# HRT.net
KiCad netlist of a schematic drawn in Altium Designer
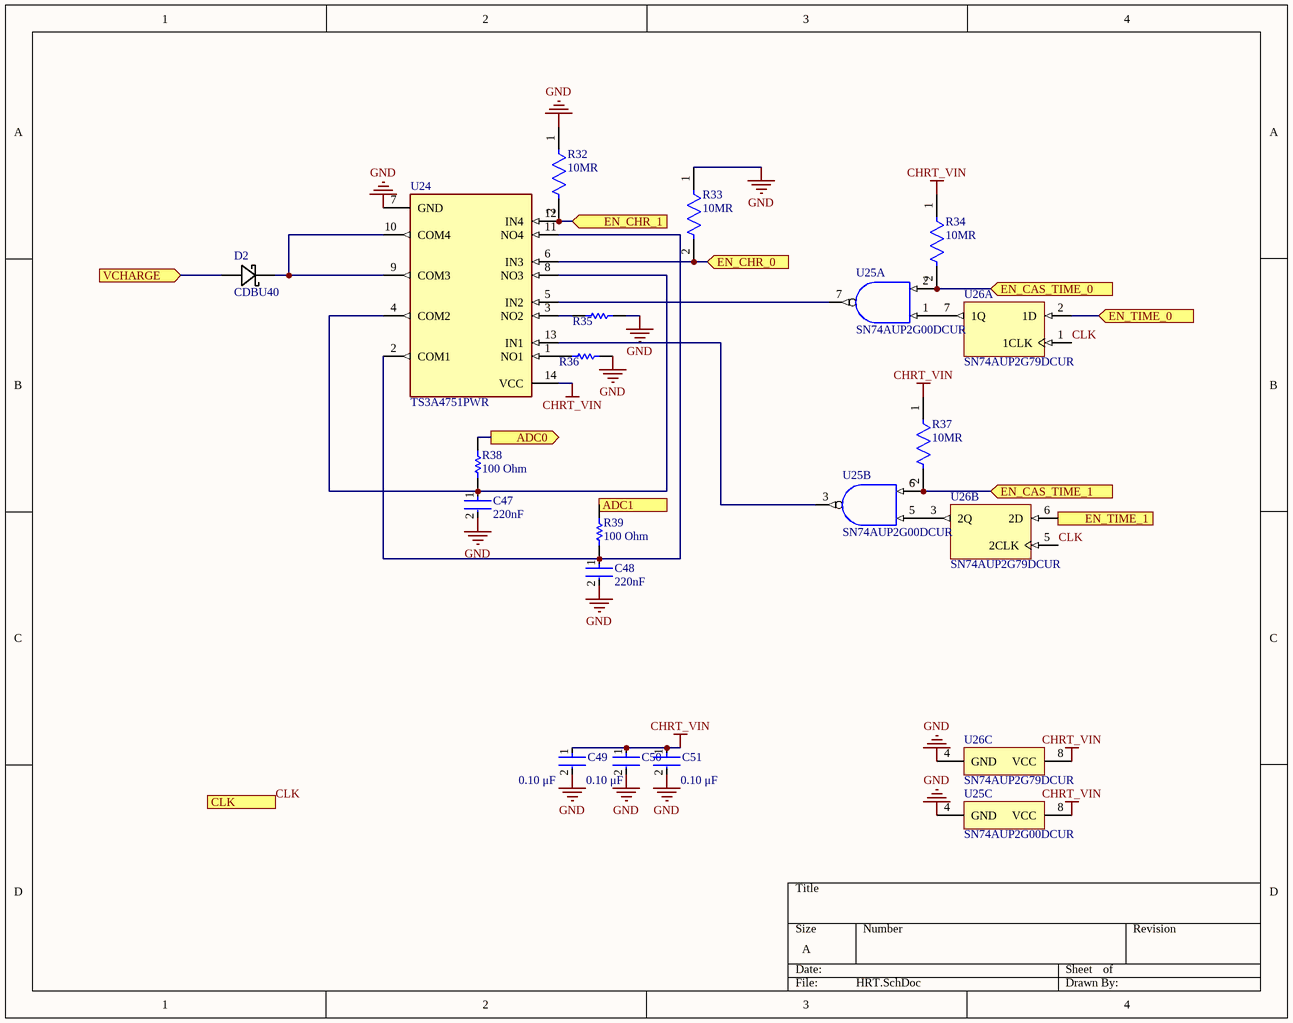
[diagram p0: HRT.SchDoc]

(export (version "E")
  (design (tool "Eeschema 10.0.6"))
  (components
    (comp (ref "C47")
      (value "GRM155R71C224KA12D")
      (footprint "FP-GRM155-0_05-IPC_C")
      (description "Chip Multilayer Ceramic Capacitors for General Purpose, 0402, 0.22uF, X7R, 15%, 10%, 16V")
      (fields
        (field (name "CAPACITANCE") "220nF")
        (field (name "VOLTAGE") "16V")
        (field (name "TOLERANCE") "10%")
      )
      (libsource (lib "Altium Content Vault") (part "02cd4be3c70576c341d710602a673aa"))
    )
    (comp (ref "C48")
      (value "GRM155R71C224KA12D")
      (footprint "FP-GRM155-0_05-IPC_C")
      (description "Chip Multilayer Ceramic Capacitors for General Purpose, 0402, 0.22uF, X7R, 15%, 10%, 16V")
      (fields
        (field (name "CAPACITANCE") "220nF")
        (field (name "VOLTAGE") "16V")
        (field (name "TOLERANCE") "10%")
      )
      (libsource (lib "Altium Content Vault") (part "02cd4be3c70576c341d710602a673aa"))
    )
    (comp (ref "C49")
      (value "C0402C104K8PACTU")
      (footprint "FP-C0402-BB-MFG")
      (description "CAP CER 0.1UF 10V X5R 0402")
      (fields
        (field (name "CAPACITANCE") "0.10 μF")
        (field (name "MANUFACTURER") "Kemet")
        (field (name "TOLERANCE") "0.1")
      )
      (libsource (lib "Altium Content Vault") (part "b4654b650e69147ec39a6b967a45e02"))
    )
    (comp (ref "C50")
      (value "C0402C104K8PACTU")
      (footprint "FP-C0402-BB-MFG")
      (description "CAP CER 0.1UF 10V X5R 0402")
      (fields
        (field (name "CAPACITANCE") "0.10 μF")
        (field (name "MANUFACTURER") "Kemet")
        (field (name "TOLERANCE") "0.1")
      )
      (libsource (lib "Altium Content Vault") (part "b4654b650e69147ec39a6b967a45e02"))
    )
    (comp (ref "C51")
      (value "C0402C104K8PACTU")
      (footprint "FP-C0402-BB-MFG")
      (description "CAP CER 0.1UF 10V X5R 0402")
      (fields
        (field (name "CAPACITANCE") "0.10 μF")
        (field (name "MANUFACTURER") "Kemet")
        (field (name "TOLERANCE") "0.1")
      )
      (libsource (lib "Altium Content Vault") (part "b4654b650e69147ec39a6b967a45e02"))
    )
    (comp (ref "D2")
      (value "CDBU40")
      (footprint "CDBU")
      (description "No Description Available")
      (fields (field (name "COPYRIGHT") "Copyright (C) 2022 Ultra Librarian. All rights reserved."))
      (libsource (lib "CDBU40") (part "CDBU40"))
    )
    (comp (ref "R32")
      (value "CRCW040210M0JNED")
      (footprint "FP-CRCW0402-e3-IPC_C")
      (description "RES Thick Film, 10MΩ, 5%, 0.063W, 200ppm/°C, 0402")
      (fields (field (name "TOLERANCE") "5%") (field (name "RESISTANCE") "10MR"))
      (libsource (lib "Altium Content Vault") (part "1029c3af85768c4190bb7ad29bc67b5"))
    )
    (comp (ref "R33")
      (value "CRCW040210M0JNED")
      (footprint "FP-CRCW0402-e3-IPC_C")
      (description "RES Thick Film, 10MΩ, 5%, 0.063W, 200ppm/°C, 0402")
      (fields (field (name "TOLERANCE") "5%") (field (name "RESISTANCE") "10MR"))
      (libsource (lib "Altium Content Vault") (part "1029c3af85768c4190bb7ad29bc67b5"))
    )
    (comp (ref "R34")
      (value "CRCW040210M0JNED")
      (footprint "FP-CRCW0402-e3-IPC_C")
      (description "RES Thick Film, 10MΩ, 5%, 0.063W, 200ppm/°C, 0402")
      (fields (field (name "TOLERANCE") "5%") (field (name "RESISTANCE") "10MR"))
      (libsource (lib "Altium Content Vault") (part "1029c3af85768c4190bb7ad29bc67b5"))
    )
    (comp (ref "R35")
      (value "CRCW040222R0FKED")
      (footprint "RESC1005X40X25LL05T05")
      (fields (field (name "MANUFACTURER") "Vishay Dale"))
      (libsource (lib "Altium Content Vault") (part "RES"))
    )
    (comp (ref "R36")
      (value "CRCW040222R0FKED")
      (footprint "RESC1005X40X25LL05T05")
      (fields (field (name "MANUFACTURER") "Vishay Dale"))
      (libsource (lib "Altium Content Vault") (part "RES"))
    )
    (comp (ref "R37")
      (value "CRCW040210M0JNED")
      (footprint "FP-CRCW0402-e3-IPC_C")
      (description "RES Thick Film, 10MΩ, 5%, 0.063W, 200ppm/°C, 0402")
      (fields (field (name "TOLERANCE") "5%") (field (name "RESISTANCE") "10MR"))
      (libsource (lib "Altium Content Vault") (part "1029c3af85768c4190bb7ad29bc67b5"))
    )
    (comp (ref "R38")
      (value "ERJ-2RKF1000X")
      (footprint "RESC1005X40X25LL05T05")
      (description "Chip Resistor, 100 Ohm, +/- 1%, 100 mW, -55 to 155 degC, 0402 (1005 Metric), RoHS, Tape and Reel")
      (fields
        (field (name "MANUFACTURER") "Basic Passives")
        (field (name "TOLERANCE") "1%")
        (field (name "RESISTANCE") "100 Ohm")
      )
      (libsource (lib "Altium Content Vault") (part "RES-2"))
    )
    (comp (ref "R39")
      (value "ERJ-2RKF1000X")
      (footprint "RESC1005X40X25LL05T05")
      (description "Chip Resistor, 100 Ohm, +/- 1%, 100 mW, -55 to 155 degC, 0402 (1005 Metric), RoHS, Tape and Reel")
      (fields
        (field (name "MANUFACTURER") "Basic Passives")
        (field (name "TOLERANCE") "1%")
        (field (name "RESISTANCE") "100 Ohm")
      )
      (libsource (lib "Altium Content Vault") (part "RES-2"))
    )
    (comp (ref "U24")
      (value "TS3A4751PWR")
      (footprint "FP-PW0014A-IPC_C")
      (description "IC SWITCH QUAD SPST 14TSSOP")
      (libsource (lib "Altium Content Vault") (part "75fdcfb842d41a92b92a478e82e68ae"))
    )
    (comp (ref "U25")
      (value "SN74AUP2G00DCUR")
      (footprint "DCU0008A_L")
      (description "Low-Power Dual 2-Input Positive-NAND Gate, DCU0008A, LARGE T&R")
      (fields
        (field (name "GENERIC PART NUMBER") "SN74AUP2G00")
        (field (name "MANUFACTURER") "Texas Instruments")
      )
      (libsource (lib "Altium Content Vault") (part "TI-SN74XXX2GXXX-8"))
    )
    (comp (ref "U26")
      (value "SN74AUP2G79DCUR")
      (footprint "DCU0008A_L")
      (description "Low-Power Dual Positive-Edge-Triggered D-Type Flip-Flop, DCU0008A, LARGE T&R")
      (fields
        (field (name "MANUFACTURER") "Texas Instruments")
        (field (name "GENERIC PART NUMBER") "SN74AUP2G79")
      )
      (libsource (lib "Altium Content Vault") (part "TI-SN74XXX2G79-8_A"))
    )
  )
  (nets
    (net (code "1") (name "/ADC0") (class "Default")
      (node (ref "R38") (pin "2") (pinfunction "2_2") (pintype "passive"))
    )
    (net (code "2") (name "/ADC1") (class "Default")
      (node (ref "R39") (pin "2") (pinfunction "2_2") (pintype "passive"))
    )
    (net (code "3") (name "/CLK") (class "Default")
      (node (ref "U26") (pin "1") (pinfunction "1CLK_1") (pintype "input"))
      (node (ref "U26") (pin "5") (pinfunction "2CLK_5") (pintype "input"))
    )
    (net (code "4") (name "/EN_CAS_TIME_0") (class "Default")
      (node (ref "R34") (pin "2") (pinfunction "2_2") (pintype "passive"))
      (node (ref "U25") (pin "2") (pinfunction "1B_2") (pintype "input"))
    )
    (net (code "5") (name "/EN_CAS_TIME_1") (class "Default")
      (node (ref "R37") (pin "2") (pinfunction "2_2") (pintype "passive"))
      (node (ref "U25") (pin "6") (pinfunction "2B_6") (pintype "input"))
    )
    (net (code "6") (name "/EN_CHR_0") (class "Default")
      (node (ref "R33") (pin "2") (pinfunction "2_2") (pintype "passive"))
      (node (ref "U24") (pin "6") (pinfunction "IN3_6") (pintype "input"))
    )
    (net (code "7") (name "/EN_CHR_1") (class "Default")
      (node (ref "R32") (pin "2") (pinfunction "2_2") (pintype "passive"))
      (node (ref "U24") (pin "12") (pinfunction "IN4_12") (pintype "input"))
    )
    (net (code "8") (name "/EN_TIME_0") (class "Default")
      (node (ref "U26") (pin "2") (pinfunction "1D_2") (pintype "input"))
    )
    (net (code "9") (name "/EN_TIME_1") (class "Default")
      (node (ref "U26") (pin "6") (pinfunction "2D_6") (pintype "input"))
    )
    (net (code "10") (name "/VCHARGE") (class "Default")
      (node (ref "D2") (pin "2") (pinfunction "2_2") (pintype "passive"))
    )
    (net (code "11") (name "CHRT_VIN") (class "Default")
      (node (ref "C49") (pin "1") (pinfunction "1_1") (pintype "passive"))
      (node (ref "C50") (pin "1") (pinfunction "1_1") (pintype "passive"))
      (node (ref "C51") (pin "1") (pinfunction "1_1") (pintype "passive"))
      (node (ref "R34") (pin "1") (pinfunction "1_1") (pintype "passive"))
      (node (ref "R37") (pin "1") (pinfunction "1_1") (pintype "passive"))
      (node (ref "U24") (pin "14") (pinfunction "VCC_14") (pintype "power_in"))
      (node (ref "U25") (pin "8") (pinfunction "VCC_8") (pintype "power_in"))
      (node (ref "U26") (pin "8") (pinfunction "VCC_8") (pintype "power_in"))
    )
    (net (code "12") (name "GND") (class "Default")
      (node (ref "C47") (pin "2") (pinfunction "2_2") (pintype "passive"))
      (node (ref "C48") (pin "2") (pinfunction "2_2") (pintype "passive"))
      (node (ref "C49") (pin "2") (pinfunction "2_2") (pintype "passive"))
      (node (ref "C50") (pin "2") (pinfunction "2_2") (pintype "passive"))
      (node (ref "C51") (pin "2") (pinfunction "2_2") (pintype "passive"))
      (node (ref "R32") (pin "1") (pinfunction "1_1") (pintype "passive"))
      (node (ref "R33") (pin "1") (pinfunction "1_1") (pintype "passive"))
      (node (ref "R35") (pin "2") (pinfunction "2_2") (pintype "passive"))
      (node (ref "R36") (pin "2") (pinfunction "2_2") (pintype "passive"))
      (node (ref "U24") (pin "7") (pinfunction "GND_7") (pintype "power_in"))
      (node (ref "U25") (pin "4") (pinfunction "GND_4") (pintype "power_in"))
      (node (ref "U26") (pin "4") (pinfunction "GND_4") (pintype "power_in"))
    )
    (net (code "13") (name "Net-(U24-COM1)") (class "Default")
      (node (ref "C48") (pin "1") (pinfunction "1_1") (pintype "passive"))
      (node (ref "R39") (pin "1") (pinfunction "1_1") (pintype "passive"))
      (node (ref "U24") (pin "11") (pinfunction "NO4_11") (pintype "input"))
      (node (ref "U24") (pin "2") (pinfunction "COM1_2") (pintype "output"))
    )
    (net (code "14") (name "Net-(U24-COM2)") (class "Default")
      (node (ref "C47") (pin "1") (pinfunction "1_1") (pintype "passive"))
      (node (ref "R38") (pin "1") (pinfunction "1_1") (pintype "passive"))
      (node (ref "U24") (pin "4") (pinfunction "COM2_4") (pintype "output"))
      (node (ref "U24") (pin "8") (pinfunction "NO3_8") (pintype "input"))
    )
    (net (code "15") (name "Net-(U24-COM3)") (class "Default")
      (node (ref "D2") (pin "1") (pinfunction "1_1") (pintype "passive"))
      (node (ref "U24") (pin "10") (pinfunction "COM4_10") (pintype "output"))
      (node (ref "U24") (pin "9") (pinfunction "COM3_9") (pintype "output"))
    )
    (net (code "16") (name "Net-(U24-IN1)") (class "Default")
      (node (ref "U24") (pin "13") (pinfunction "IN1_13") (pintype "input"))
      (node (ref "U25") (pin "3") (pinfunction "2Y_3") (pintype "output"))
    )
    (net (code "17") (name "Net-(U24-IN2)") (class "Default")
      (node (ref "U24") (pin "5") (pinfunction "IN2_5") (pintype "input"))
      (node (ref "U25") (pin "7") (pinfunction "1Y_7") (pintype "output"))
    )
    (net (code "18") (name "Net-(U24-NO1)") (class "Default")
      (node (ref "R36") (pin "1") (pinfunction "1_1") (pintype "passive"))
      (node (ref "U24") (pin "1") (pinfunction "NO1_1") (pintype "input"))
    )
    (net (code "19") (name "Net-(U24-NO2)") (class "Default")
      (node (ref "R35") (pin "1") (pinfunction "1_1") (pintype "passive"))
      (node (ref "U24") (pin "3") (pinfunction "NO2_3") (pintype "input"))
    )
    (net (code "20") (name "Net-(U25A-1A)") (class "Default")
      (node (ref "U25") (pin "1") (pinfunction "1A_1") (pintype "input"))
      (node (ref "U26") (pin "7") (pinfunction "1Q_7") (pintype "output"))
    )
    (net (code "21") (name "Net-(U25B-2A)") (class "Default")
      (node (ref "U25") (pin "5") (pinfunction "2A_5") (pintype "input"))
      (node (ref "U26") (pin "3") (pinfunction "2Q_3") (pintype "output"))
    )
  )
)
